# ACS_5_1.net
KiCad netlist of a schematic drawn in EAGLE
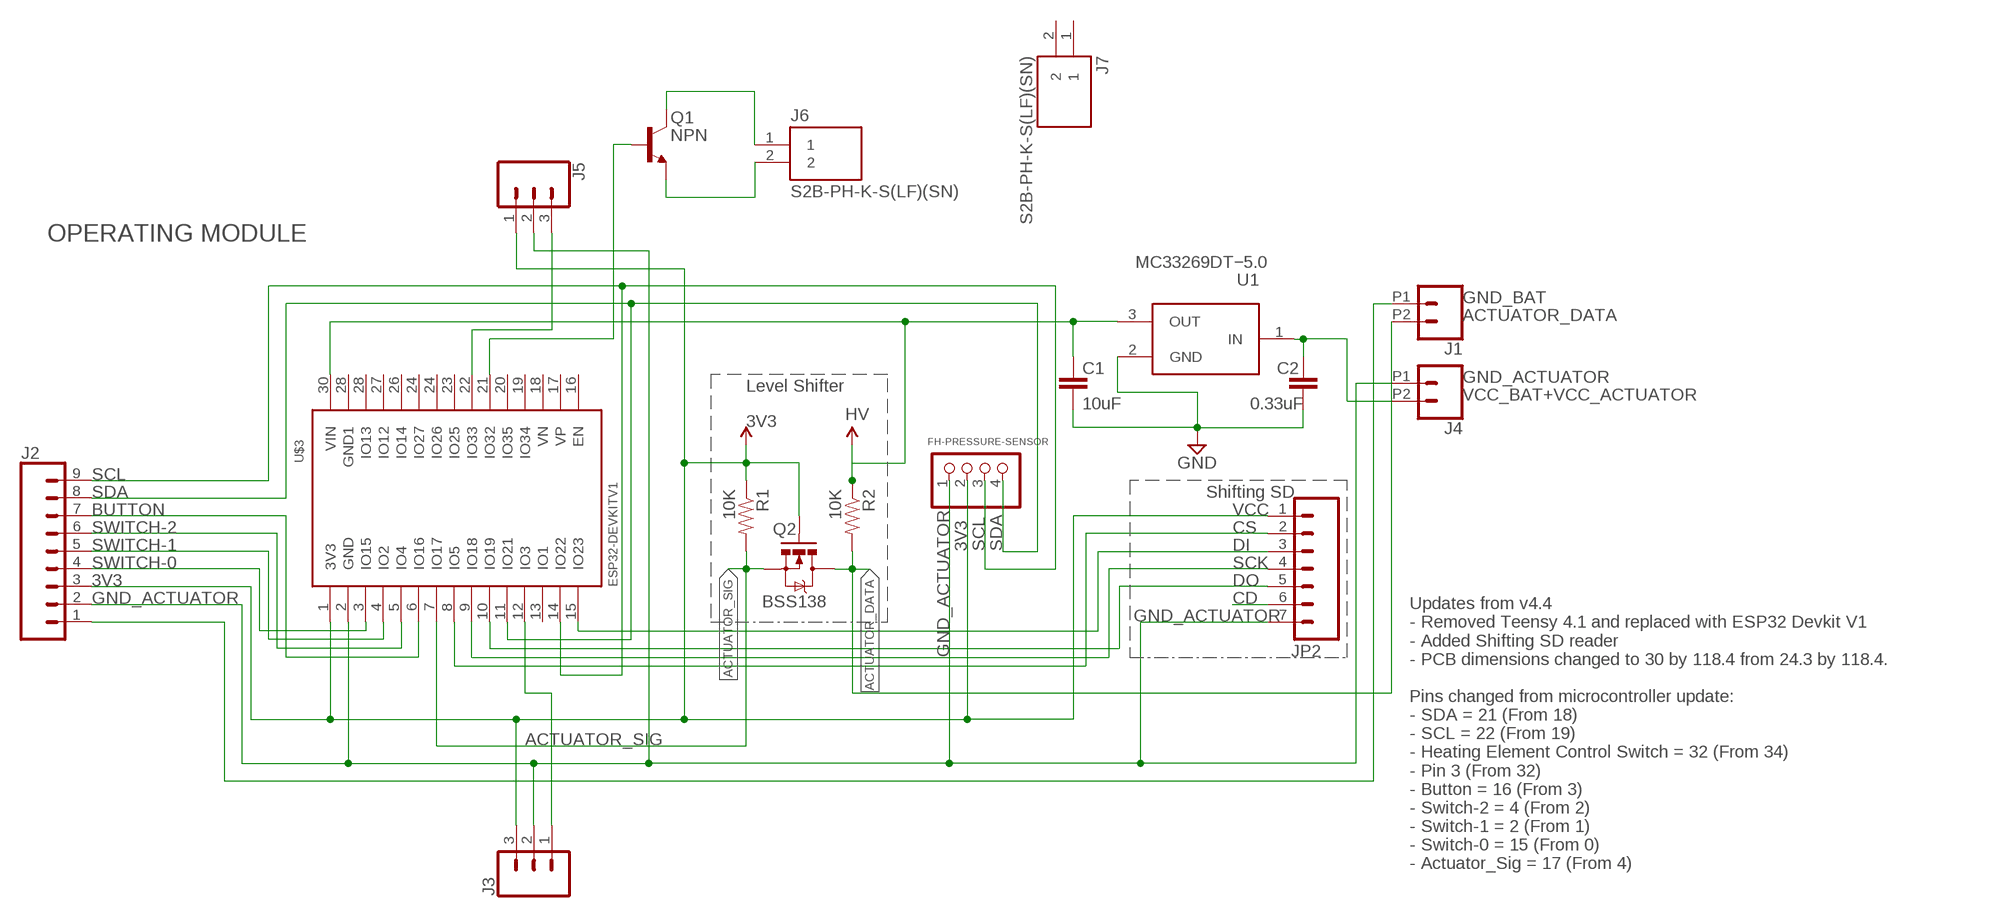
[diagram p0: schematic, sheet 1]

(export (version "E")
  (design (tool "Eeschema 10.0.6"))
  (components
    (comp (ref "C1")
      (value "10uF")
      (footprint "eagle-import:CAPC1608X85")
      (libsource (lib "eagle-import") (part "CCHIP-0603(1608-METRIC)_"))
    )
    (comp (ref "C2")
      (value "0.33uF")
      (footprint "eagle-import:CAPC1608X85")
      (libsource (lib "eagle-import") (part "CCHIP-0603(1608-METRIC)_"))
    )
    (comp (ref "FH-PRESSURE-SENSOR")
      (value "PINHD-1X4")
      (footprint "eagle-import:1X04")
      (libsource (lib "eagle-import") (part "PINHD-1X4"))
    )
    (comp (ref "J1")
      (value "CONN_022.54MM_SCREWTERM")
      (footprint "eagle-import:1X02_2.54_SCREWTERM")
      (libsource (lib "eagle-import") (part "CONN_022.54MM_SCREWTERM"))
    )
    (comp (ref "J2")
      (value "CONN_09")
      (footprint "eagle-import:1X09")
      (libsource (lib "eagle-import") (part "CONN_09"))
    )
    (comp (ref "J3")
      (value "CONN_03")
      (footprint "eagle-import:1X03")
      (libsource (lib "eagle-import") (part "CONN_03"))
    )
    (comp (ref "J4")
      (value "CONN_022.54MM_SCREWTERM")
      (footprint "eagle-import:1X02_2.54_SCREWTERM")
      (libsource (lib "eagle-import") (part "CONN_022.54MM_SCREWTERM"))
    )
    (comp (ref "J5")
      (value "CONN_03")
      (footprint "eagle-import:1X03")
      (libsource (lib "eagle-import") (part "CONN_03"))
    )
    (comp (ref "J6")
      (value "S2B-PH-K-S(LF)(SN)")
      (footprint "eagle-import:JST_S2B-PH-K-S(LF)(SN)")
      (fields (field (name "MF") "JST Sales America Inc."))
      (libsource (lib "eagle-import") (part "S2B-PH-K-S(LF)(SN)"))
    )
    (comp (ref "J7")
      (value "S2B-PH-K-S(LF)(SN)")
      (footprint "eagle-import:JST_S2B-PH-K-S(LF)(SN)")
      (fields (field (name "MF") "JST Sales America Inc."))
      (libsource (lib "eagle-import") (part "S2B-PH-K-S(LF)(SN)"))
    )
    (comp (ref "JP2")
      (value "M07")
      (footprint "eagle-import:1X07")
      (libsource (lib "eagle-import") (part "M07"))
    )
    (comp (ref "Q1")
      (value "NPN")
      (footprint "eagle-import:SOT95P237X112-3N")
      (libsource (lib "eagle-import") (part "NPNSOT23_"))
    )
    (comp (ref "Q2")
      (value "BSS138")
      (footprint "eagle-import:SOT23-3")
      (libsource (lib "eagle-import") (part "MOSFET-NCHANNELSMD"))
    )
    (comp (ref "R1")
      (value "10K")
      (footprint "eagle-import:0603-RES")
      (libsource (lib "eagle-import") (part "RESISTOR0603-RES"))
    )
    (comp (ref "R2")
      (value "10K")
      (footprint "eagle-import:0603-RES")
      (libsource (lib "eagle-import") (part "RESISTOR0603-RES"))
    )
    (comp (ref "U$3")
      (value "ESP32DEVKITV1")
      (footprint "eagle-import:ESP32-DEVKITV1")
      (libsource (lib "eagle-import") (part "ESP32DEVKITV1"))
    )
    (comp (ref "U1")
      (value "MC78M05BDTRKG")
      (footprint "eagle-import:MC78M05BDTRKG")
      (fields
        (field (name "MANUFACTURER") "ON Semiconductor")
        (field (name "MPN") "IC REG LINEAR 5V 500MA DPAK")
        (field (name "CREATED_BY") "PCBLayout.com")
      )
      (libsource (lib "eagle-import") (part "MC78M05BDTRKG"))
    )
  )
  (nets
    (net (code "1") (name "/BUTTON") (class "Default")
      (node (ref "J2") (pin "7") (pinfunction "7_7") (pintype "passive"))
      (node (ref "U$3") (pin "6") (pinfunction "IO16_6") (pintype "bidirectional"))
    )
    (net (code "2") (name "/GND_ACTUATOR") (class "Default")
      (node (ref "FH-PRESSURE-SENSOR") (pin "1") (pinfunction "1_1") (pintype "passive"))
      (node (ref "J2") (pin "2") (pinfunction "2_2") (pintype "passive"))
      (node (ref "J3") (pin "2") (pinfunction "2_2") (pintype "passive"))
      (node (ref "J4") (pin "P1") (pinfunction "1_P1") (pintype "passive"))
      (node (ref "J5") (pin "2") (pinfunction "2_2") (pintype "passive"))
      (node (ref "JP2") (pin "7") (pinfunction "7_7") (pintype "passive"))
      (node (ref "U$3") (pin "2") (pinfunction "GND_2") (pintype "bidirectional"))
    )
    (net (code "3") (name "/GND_BAT") (class "Default")
      (node (ref "J1") (pin "P1") (pinfunction "1_P1") (pintype "passive"))
      (node (ref "J2") (pin "1") (pinfunction "1_1") (pintype "passive"))
    )
    (net (code "4") (name "/SCL") (class "Default")
      (node (ref "FH-PRESSURE-SENSOR") (pin "3") (pinfunction "3_3") (pintype "passive"))
      (node (ref "J2") (pin "9") (pinfunction "9_9") (pintype "passive"))
      (node (ref "U$3") (pin "14") (pinfunction "IO22_14") (pintype "bidirectional"))
    )
    (net (code "5") (name "/SDA") (class "Default")
      (node (ref "FH-PRESSURE-SENSOR") (pin "4") (pinfunction "4_4") (pintype "passive"))
      (node (ref "J2") (pin "8") (pinfunction "8_8") (pintype "passive"))
      (node (ref "U$3") (pin "11") (pinfunction "IO21_11") (pintype "bidirectional"))
    )
    (net (code "6") (name "/SWITCH-0") (class "Default")
      (node (ref "J2") (pin "4") (pinfunction "4_4") (pintype "passive"))
      (node (ref "U$3") (pin "3") (pinfunction "IO15_3") (pintype "bidirectional"))
    )
    (net (code "7") (name "/SWITCH-1") (class "Default")
      (node (ref "J2") (pin "5") (pinfunction "5_5") (pintype "passive"))
      (node (ref "U$3") (pin "4") (pinfunction "IO2_4") (pintype "bidirectional"))
    )
    (net (code "8") (name "/SWITCH-2") (class "Default")
      (node (ref "J2") (pin "6") (pinfunction "6_6") (pintype "passive"))
      (node (ref "U$3") (pin "5") (pinfunction "IO4_5") (pintype "bidirectional"))
    )
    (net (code "9") (name "/VCC_BAT+VCC_ACTUATOR") (class "Default")
      (node (ref "C2") (pin "1") (pinfunction "1_1") (pintype "passive"))
      (node (ref "J4") (pin "P2") (pinfunction "2_P2") (pintype "passive"))
      (node (ref "U1") (pin "1") (pinfunction "IN_1") (pintype "input"))
    )
    (net (code "10") (name "ACTUATOR_DATA") (class "Default")
      (node (ref "J1") (pin "P2") (pinfunction "2_P2") (pintype "passive"))
      (node (ref "Q2") (pin "3") (pinfunction "D_3") (pintype "passive"))
      (node (ref "R2") (pin "2") (pinfunction "2_2") (pintype "passive"))
    )
    (net (code "11") (name "ACTUATOR_SIG") (class "Default")
      (node (ref "Q2") (pin "2") (pinfunction "S_2") (pintype "passive"))
      (node (ref "R1") (pin "2") (pinfunction "2_2") (pintype "passive"))
      (node (ref "U$3") (pin "7") (pinfunction "IO17_7") (pintype "bidirectional"))
    )
    (net (code "12") (name "GND") (class "Default")
      (node (ref "C1") (pin "2") (pinfunction "2_2") (pintype "passive"))
      (node (ref "C2") (pin "2") (pinfunction "2_2") (pintype "passive"))
      (node (ref "U1") (pin "2") (pinfunction "GND_2") (pintype "power_in"))
    )
    (net (code "13") (name "HV") (class "Default")
      (node (ref "C1") (pin "1") (pinfunction "1_1") (pintype "passive"))
      (node (ref "R2") (pin "1") (pinfunction "1_1") (pintype "passive"))
      (node (ref "U$3") (pin "30") (pinfunction "VIN_30") (pintype "bidirectional"))
      (node (ref "U1") (pin "3") (pinfunction "OUT_3") (pintype "output"))
    )
    (net (code "14") (name "LV") (class "Default")
      (node (ref "FH-PRESSURE-SENSOR") (pin "2") (pinfunction "2_2") (pintype "passive"))
      (node (ref "J2") (pin "3") (pinfunction "3_3") (pintype "passive"))
      (node (ref "J3") (pin "3") (pinfunction "3_3") (pintype "passive"))
      (node (ref "J5") (pin "1") (pinfunction "1_1") (pintype "passive"))
      (node (ref "JP2") (pin "1") (pinfunction "1_1") (pintype "passive"))
      (node (ref "Q2") (pin "1") (pinfunction "G_1") (pintype "passive"))
      (node (ref "R1") (pin "1") (pinfunction "1_1") (pintype "passive"))
      (node (ref "U$3") (pin "1") (pinfunction "3V3_1") (pintype "bidirectional"))
    )
    (net (code "15") (name "Net-(Q1-B)") (class "Default")
      (node (ref "Q1") (pin "2") (pinfunction "B_2") (pintype "passive"))
      (node (ref "U$3") (pin "21") (pinfunction "IO32_21") (pintype "bidirectional"))
    )
    (net (code "16") (name "Net-(Q1-C)") (class "Default")
      (node (ref "J6") (pin "1") (pinfunction "1_1") (pintype "passive"))
      (node (ref "Q1") (pin "3") (pinfunction "C_3") (pintype "passive"))
    )
    (net (code "17") (name "Net-(Q1-E)") (class "Default")
      (node (ref "J6") (pin "2") (pinfunction "2_2") (pintype "passive"))
      (node (ref "Q1") (pin "1") (pinfunction "E_1") (pintype "passive"))
    )
    (net (code "18") (name "Net-(U$3-IO3)") (class "Default")
      (node (ref "J3") (pin "1") (pinfunction "1_1") (pintype "passive"))
      (node (ref "U$3") (pin "12") (pinfunction "IO3_12") (pintype "bidirectional"))
    )
    (net (code "19") (name "Net-(U$3-IO5)") (class "Default")
      (node (ref "JP2") (pin "2") (pinfunction "2_2") (pintype "passive"))
      (node (ref "U$3") (pin "8") (pinfunction "IO5_8") (pintype "bidirectional"))
    )
    (net (code "20") (name "Net-(U$3-IO18)") (class "Default")
      (node (ref "JP2") (pin "4") (pinfunction "4_4") (pintype "passive"))
      (node (ref "U$3") (pin "9") (pinfunction "IO18_9") (pintype "bidirectional"))
    )
    (net (code "21") (name "Net-(U$3-IO19)") (class "Default")
      (node (ref "JP2") (pin "5") (pinfunction "5_5") (pintype "passive"))
      (node (ref "U$3") (pin "10") (pinfunction "IO19_10") (pintype "bidirectional"))
    )
    (net (code "22") (name "Net-(U$3-IO23)") (class "Default")
      (node (ref "JP2") (pin "3") (pinfunction "3_3") (pintype "passive"))
      (node (ref "U$3") (pin "15") (pinfunction "IO23_15") (pintype "bidirectional"))
    )
    (net (code "23") (name "Net-(U$3-IO33)") (class "Default")
      (node (ref "J5") (pin "3") (pinfunction "3_3") (pintype "passive"))
      (node (ref "U$3") (pin "22") (pinfunction "IO33_22") (pintype "bidirectional"))
    )
    (net (code "24") (name "unconnected-(J7-Pad1)") (class "Default")
      (node (ref "J7") (pin "1") (pinfunction "1_1") (pintype "passive"))
    )
    (net (code "25") (name "unconnected-(J7-Pad2)") (class "Default")
      (node (ref "J7") (pin "2") (pinfunction "2_2") (pintype "passive"))
    )
    (net (code "26") (name "unconnected-(JP2-Pad6)") (class "Default")
      (node (ref "JP2") (pin "6") (pinfunction "6_6") (pintype "passive"))
    )
    (net (code "27") (name "unconnected-(U$3-EN-Pad16)") (class "Default")
      (node (ref "U$3") (pin "16") (pinfunction "EN_16") (pintype "bidirectional"))
    )
    (net (code "28") (name "unconnected-(U$3-GND1-Pad28)") (class "Default")
      (node (ref "U$3") (pin "28") (pinfunction "GND1_28") (pintype "bidirectional"))
    )
    (net (code "29") (name "unconnected-(U$3-IO1-Pad13)") (class "Default")
      (node (ref "U$3") (pin "13") (pinfunction "IO1_13") (pintype "bidirectional"))
    )
    (net (code "30") (name "unconnected-(U$3-IO12-Pad27)") (class "Default")
      (node (ref "U$3") (pin "27") (pinfunction "IO12_27") (pintype "bidirectional"))
    )
    (net (code "31") (name "unconnected-(U$3-IO13-Pad28)") (class "Default")
      (node (ref "U$3") (pin "28") (pinfunction "IO13_28") (pintype "bidirectional"))
    )
    (net (code "32") (name "unconnected-(U$3-IO14-Pad26)") (class "Default")
      (node (ref "U$3") (pin "26") (pinfunction "IO14_26") (pintype "bidirectional"))
    )
    (net (code "33") (name "unconnected-(U$3-IO25-Pad23)") (class "Default")
      (node (ref "U$3") (pin "23") (pinfunction "IO25_23") (pintype "bidirectional"))
    )
    (net (code "34") (name "unconnected-(U$3-IO26-Pad24)") (class "Default")
      (node (ref "U$3") (pin "24") (pinfunction "IO26_24") (pintype "bidirectional"))
    )
    (net (code "35") (name "unconnected-(U$3-IO27-Pad24)") (class "Default")
      (node (ref "U$3") (pin "24") (pinfunction "IO27_24") (pintype "bidirectional"))
    )
    (net (code "36") (name "unconnected-(U$3-IO34-Pad19)") (class "Default")
      (node (ref "U$3") (pin "19") (pinfunction "IO34_19") (pintype "bidirectional"))
    )
    (net (code "37") (name "unconnected-(U$3-IO35-Pad20)") (class "Default")
      (node (ref "U$3") (pin "20") (pinfunction "IO35_20") (pintype "bidirectional"))
    )
    (net (code "38") (name "unconnected-(U$3-VN-Pad18)") (class "Default")
      (node (ref "U$3") (pin "18") (pinfunction "VN_18") (pintype "bidirectional"))
    )
    (net (code "39") (name "unconnected-(U$3-VP-Pad17)") (class "Default")
      (node (ref "U$3") (pin "17") (pinfunction "VP_17") (pintype "bidirectional"))
    )
  )
)
